# STM32.net
KiCad netlist of a schematic drawn in Altium Designer
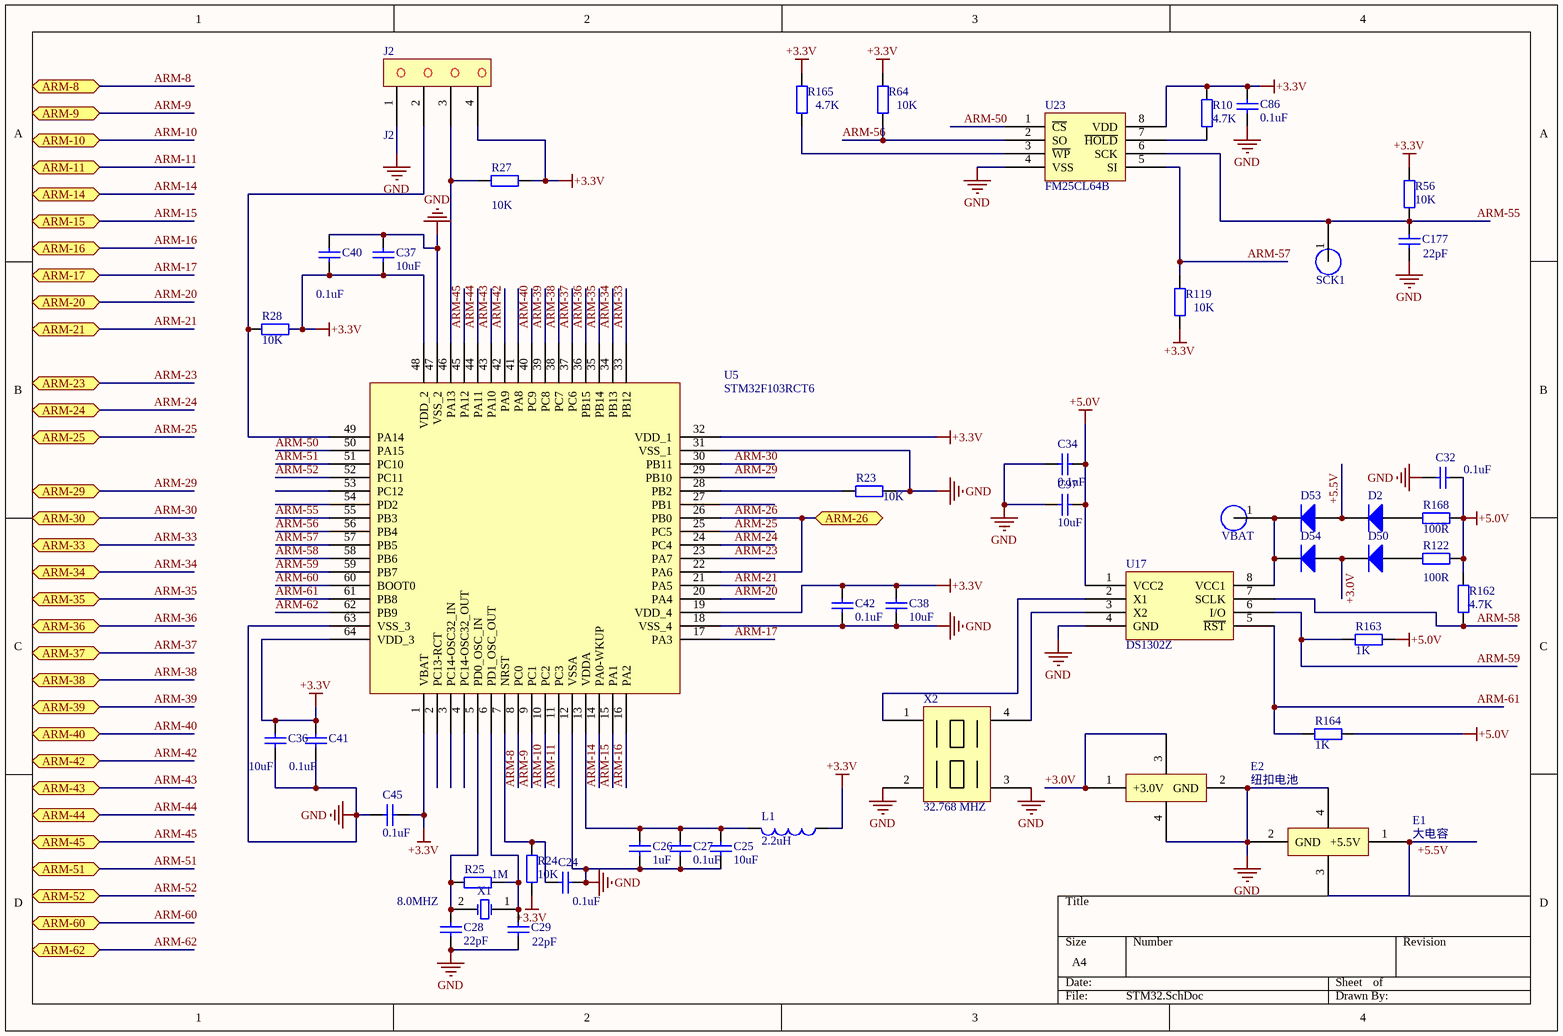
[diagram p0: STM32.SchDoc]

(export (version "E")
  (design (tool "Eeschema 10.0.6"))
  (components
    (comp (ref "C24")
      (value "0.1uF")
      (footprint "采集板3.0增加1路模拟量2:C0805")
      (description "Capacitor")
      (fields (field (name "Comment") "Cap") (field (name "PUBLISHER") "Altium Limited"))
      (libsource (lib "Miscellaneous Devices") (part "Cap"))
    )
    (comp (ref "C25")
      (value "10uF")
      (footprint "C1206")
      (description "Capacitor")
      (fields (field (name "Comment") "Cap") (field (name "PUBLISHER") "Altium Limited"))
      (libsource (lib "Miscellaneous Devices") (part "Cap"))
    )
    (comp (ref "C26")
      (value "1uF")
      (footprint "C0805")
      (description "Capacitor")
      (fields (field (name "Comment") "Cap") (field (name "PUBLISHER") "Altium Limited"))
      (libsource (lib "Miscellaneous Devices") (part "Cap"))
    )
    (comp (ref "C27")
      (value "0.1uF")
      (footprint "采集板3.0增加1路模拟量2:C0805")
      (description "Capacitor")
      (fields (field (name "Comment") "Cap") (field (name "PUBLISHER") "Altium Limited"))
      (libsource (lib "Miscellaneous Devices") (part "Cap"))
    )
    (comp (ref "C28")
      (value "22pF")
      (footprint "采集板3.0增加1路模拟量2:C0805")
      (description "Capacitor")
      (fields (field (name "Comment") "Cap") (field (name "PUBLISHER") "Altium Limited"))
      (libsource (lib "Miscellaneous Devices") (part "Cap"))
    )
    (comp (ref "C29")
      (value "22pF")
      (footprint "采集板3.0增加1路模拟量2:C0805")
      (description "Capacitor")
      (fields (field (name "Comment") "Cap") (field (name "PUBLISHER") "Altium Limited"))
      (libsource (lib "Miscellaneous Devices") (part "Cap"))
    )
    (comp (ref "C32")
      (value "0.1uF")
      (footprint "采集板3.0增加1路模拟量2:C0805")
      (description "Capacitor")
      (fields (field (name "Comment") "Cap") (field (name "PUBLISHER") "Altium Limited"))
      (libsource (lib "Miscellaneous Devices") (part "Cap"))
    )
    (comp (ref "C34")
      (value "0.1uF")
      (footprint "采集板3.0增加1路模拟量2:C0805")
      (description "Capacitor")
      (fields (field (name "Comment") "Cap") (field (name "PUBLISHER") "Altium Limited"))
      (libsource (lib "Miscellaneous Devices") (part "Cap"))
    )
    (comp (ref "C36")
      (value "10uF")
      (footprint "C1206")
      (description "Capacitor")
      (fields (field (name "Comment") "Cap") (field (name "PUBLISHER") "Altium Limited"))
      (libsource (lib "Miscellaneous Devices") (part "Cap"))
    )
    (comp (ref "C37")
      (value "10uF")
      (footprint "C1206")
      (description "Capacitor")
      (fields (field (name "Comment") "Cap") (field (name "PUBLISHER") "Altium Limited"))
      (libsource (lib "Miscellaneous Devices") (part "Cap"))
    )
    (comp (ref "C38")
      (value "10uF")
      (footprint "C1206")
      (description "Capacitor")
      (fields (field (name "Comment") "Cap") (field (name "PUBLISHER") "Altium Limited"))
      (libsource (lib "Miscellaneous Devices") (part "Cap"))
    )
    (comp (ref "C40")
      (value "0.1uF")
      (footprint "采集板3.0增加1路模拟量2:C0805")
      (description "Capacitor")
      (fields (field (name "Comment") "Cap") (field (name "PUBLISHER") "Altium Limited"))
      (libsource (lib "Miscellaneous Devices") (part "Cap"))
    )
    (comp (ref "C41")
      (value "0.1uF")
      (footprint "采集板3.0增加1路模拟量2:C0805")
      (description "Capacitor")
      (fields (field (name "Comment") "Cap") (field (name "PUBLISHER") "Altium Limited"))
      (libsource (lib "Miscellaneous Devices") (part "Cap"))
    )
    (comp (ref "C42")
      (value "0.1uF")
      (footprint "采集板3.0增加1路模拟量2:C0805")
      (description "Capacitor")
      (fields (field (name "Comment") "Cap") (field (name "PUBLISHER") "Altium Limited"))
      (libsource (lib "Miscellaneous Devices") (part "Cap"))
    )
    (comp (ref "C45")
      (value "0.1uF")
      (footprint "采集板3.0增加1路模拟量2:C0805")
      (description "Capacitor")
      (fields (field (name "Comment") "Cap") (field (name "PUBLISHER") "Altium Limited"))
      (libsource (lib "Miscellaneous Devices") (part "Cap"))
    )
    (comp (ref "C86")
      (value "0.1uF")
      (footprint "C86单独封装")
      (description "Capacitor")
      (fields (field (name "Comment") "Cap") (field (name "PUBLISHER") "Altium Limited"))
      (libsource (lib "Miscellaneous Devices") (part "Cap"))
    )
    (comp (ref "C97")
      (value "10uF")
      (footprint "C1206")
      (description "Capacitor")
      (fields (field (name "Comment") "Cap") (field (name "PUBLISHER") "Altium Limited"))
      (libsource (lib "Miscellaneous Devices") (part "Cap"))
    )
    (comp (ref "C177")
      (value "22pF")
      (footprint "采集板3.0增加1路模拟量2:C0805")
      (description "Capacitor")
      (fields (field (name "Comment") "Cap") (field (name "PUBLISHER") "Altium Limited"))
      (libsource (lib "Miscellaneous Devices") (part "Cap"))
    )
    (comp (ref "D2")
      (value "Diode 1N4001")
      (footprint "SOD123")
      (description "1 Amp General Purpose Rectifier")
      (fields (field (name "PUBLISHER") "Altium Limited"))
      (libsource (lib "Miscellaneous Devices") (part "Diode 1N4001"))
    )
    (comp (ref "D50")
      (value "Diode 1N4001")
      (footprint "SOD123")
      (description "1 Amp General Purpose Rectifier")
      (fields (field (name "PUBLISHER") "Altium Limited"))
      (libsource (lib "Miscellaneous Devices") (part "Diode 1N4001"))
    )
    (comp (ref "D53")
      (value "Diode 1N4001")
      (footprint "SOD123")
      (description "1 Amp General Purpose Rectifier")
      (fields (field (name "PUBLISHER") "Altium Limited"))
      (libsource (lib "Miscellaneous Devices") (part "Diode 1N4001"))
    )
    (comp (ref "D54")
      (value "Diode 1N4001")
      (footprint "SOD123")
      (description "1 Amp General Purpose Rectifier")
      (fields (field (name "PUBLISHER") "Altium Limited"))
      (libsource (lib "Miscellaneous Devices") (part "Diode 1N4001"))
    )
    (comp (ref "E1") (value "大电容") (footprint "法拉电容电池") (libsource (lib "大电容") (part "Component_1")))
    (comp (ref "E2") (value "纽扣电池") (footprint "法拉电容电池") (libsource (lib "纽扣电池") (part "Component_1")))
    (comp (ref "J2") (value "J2") (footprint "J2DIP") (libsource (lib "J2") (part "Component_1")))
    (comp (ref "L1")
      (value "2.2uH")
      (footprint "采集板3.0增加1路模拟量2:R0805")
      (description "Inductor")
      (fields (field (name "PUBLISHER") "Altium Limited"))
      (libsource (lib "Miscellaneous Devices") (part "Inductor"))
    )
    (comp (ref "R10")
      (value "4.7K")
      (footprint "采集板3.0增加1路模拟量2:R0805")
      (description "Resistor")
      (fields (field (name "Comment") "Res2") (field (name "PUBLISHER") "Altium Limited"))
      (libsource (lib "") (part "Res2_3"))
    )
    (comp (ref "R23")
      (value "10K")
      (footprint "采集板3.0增加1路模拟量2:R0805")
      (description "Resistor")
      (fields (field (name "Comment") "Res2") (field (name "PUBLISHER") "Altium Limited"))
      (libsource (lib "Miscellaneous Devices") (part "Res2"))
    )
    (comp (ref "R24")
      (value "10K")
      (footprint "采集板3.0增加1路模拟量2:R0805")
      (description "Resistor")
      (fields (field (name "Comment") "Res2") (field (name "PUBLISHER") "Altium Limited"))
      (libsource (lib "") (part "Res2_1"))
    )
    (comp (ref "R25")
      (value "1M")
      (footprint "采集板3.0增加1路模拟量2:R0805")
      (description "Resistor")
      (fields (field (name "Comment") "Res2") (field (name "PUBLISHER") "Altium Limited"))
      (libsource (lib "") (part "Res2_2"))
    )
    (comp (ref "R27")
      (value "10K")
      (footprint "采集板3.0增加1路模拟量2:R0805")
      (description "Resistor")
      (fields (field (name "Comment") "Res2") (field (name "PUBLISHER") "Altium Limited"))
      (libsource (lib "Miscellaneous Devices") (part "Res2"))
    )
    (comp (ref "R28")
      (value "10K")
      (footprint "采集板3.0增加1路模拟量2:R0805")
      (description "Resistor")
      (fields (field (name "Comment") "Res2") (field (name "PUBLISHER") "Altium Limited"))
      (libsource (lib "Miscellaneous Devices") (part "Res2"))
    )
    (comp (ref "R56")
      (value "10K")
      (footprint "采集板3.0增加1路模拟量2:R0805")
      (description "Resistor")
      (fields (field (name "Comment") "Res2") (field (name "PUBLISHER") "Altium Limited"))
      (libsource (lib "") (part "Res2_3"))
    )
    (comp (ref "R64")
      (value "10K")
      (footprint "采集板3.0增加1路模拟量2:R0805")
      (description "Resistor")
      (fields (field (name "Comment") "Res2") (field (name "PUBLISHER") "Altium Limited"))
      (libsource (lib "") (part "Res2_1"))
    )
    (comp (ref "R119")
      (value "10K")
      (footprint "采集板3.0增加1路模拟量2:R0805")
      (description "Resistor")
      (fields (field (name "Comment") "Res2") (field (name "PUBLISHER") "Altium Limited"))
      (libsource (lib "") (part "Res2_1"))
    )
    (comp (ref "R122")
      (value "100R")
      (footprint "R1206")
      (description "Resistor")
      (fields (field (name "Comment") "Res2") (field (name "PUBLISHER") "Altium Limited"))
      (libsource (lib "Miscellaneous Devices") (part "Res2"))
    )
    (comp (ref "R162")
      (value "4.7K")
      (footprint "采集板3.0增加1路模拟量2:R0805")
      (description "Resistor")
      (fields (field (name "Comment") "Res2") (field (name "PUBLISHER") "Altium Limited"))
      (libsource (lib "") (part "Res2_3"))
    )
    (comp (ref "R163")
      (value "1K")
      (footprint "采集板3.0增加1路模拟量2:R0805")
      (description "Resistor")
      (fields (field (name "Comment") "Res2") (field (name "PUBLISHER") "Altium Limited"))
      (libsource (lib "") (part "Res2_2"))
    )
    (comp (ref "R164")
      (value "1K")
      (footprint "采集板3.0增加1路模拟量2:R0805")
      (description "Resistor")
      (fields (field (name "Comment") "Res2") (field (name "PUBLISHER") "Altium Limited"))
      (libsource (lib "Miscellaneous Devices") (part "Res2"))
    )
    (comp (ref "R165")
      (value "4.7K")
      (footprint "采集板3.0增加1路模拟量2:R0805")
      (description "Resistor")
      (fields (field (name "Comment") "Res2") (field (name "PUBLISHER") "Altium Limited"))
      (libsource (lib "") (part "Res2_1"))
    )
    (comp (ref "R168")
      (value "100R")
      (footprint "R1206")
      (description "Resistor")
      (fields (field (name "Comment") "Res2") (field (name "PUBLISHER") "Altium Limited"))
      (libsource (lib "") (part "Res2_2"))
    )
    (comp (ref "SCK1") (value "PIN") (footprint "圆形焊盘") (libsource (lib "圆孔") (part "Component_1")))
    (comp (ref "U5")
      (value "STM32F103RCT6")
      (footprint "LQFP64")
      (libsource (lib "STM32F103RCT6") (part "Component_1"))
    )
    (comp (ref "U17") (value "DS1302Z") (footprint "SOP-8") (libsource (lib "DS1302Z") (part "Component_1")))
    (comp (ref "U23")
      (value "FM25CL64B")
      (footprint "SOIC-8")
      (libsource (lib "FM25CL64B") (part "Component_1"))
    )
    (comp (ref "VBAT") (value "PIN") (footprint "圆形焊盘") (libsource (lib "") (part "Component_1_1")))
    (comp (ref "X1")
      (value "8.0MHZ")
      (footprint "5032-2P")
      (description "Crystal Oscillator")
      (fields (field (name "Comment") "XTAL") (field (name "PUBLISHER") "Altium Limited"))
      (libsource (lib "Miscellaneous Devices") (part "XTAL"))
    )
    (comp (ref "X2")
      (value "32.768 MHZ")
      (footprint "黑色3*8-4")
      (libsource (lib "4PINXT") (part "Component_1"))
    )
  )
  (nets
    (net (code "1") (name "+3.3V") (class "Default")
      (node (ref "C36") (pin "2") (pinfunction "2_2") (pintype "passive"))
      (node (ref "C37") (pin "2") (pinfunction "2_2") (pintype "passive"))
      (node (ref "C38") (pin "2") (pinfunction "2_2") (pintype "passive"))
      (node (ref "C40") (pin "1") (pinfunction "1_1") (pintype "passive"))
      (node (ref "C41") (pin "1") (pinfunction "1_1") (pintype "passive"))
      (node (ref "C42") (pin "2") (pinfunction "2_2") (pintype "passive"))
      (node (ref "C45") (pin "1") (pinfunction "1_1") (pintype "passive"))
      (node (ref "C86") (pin "2") (pinfunction "2_2") (pintype "passive"))
      (node (ref "J2") (pin "4") (pinfunction "4_4") (pintype "passive"))
      (node (ref "L1") (pin "1") (pinfunction "1_1") (pintype "passive"))
      (node (ref "R10") (pin "1") (pinfunction "1_1") (pintype "passive"))
      (node (ref "R119") (pin "1") (pinfunction "1_1") (pintype "passive"))
      (node (ref "R165") (pin "2") (pinfunction "2_2") (pintype "passive"))
      (node (ref "R24") (pin "1") (pinfunction "1_1") (pintype "passive"))
      (node (ref "R27") (pin "2") (pinfunction "2_2") (pintype "passive"))
      (node (ref "R28") (pin "2") (pinfunction "2_2") (pintype "passive"))
      (node (ref "R56") (pin "1") (pinfunction "1_1") (pintype "passive"))
      (node (ref "R64") (pin "2") (pinfunction "2_2") (pintype "passive"))
      (node (ref "U23") (pin "8") (pinfunction "VDD_8") (pintype "passive"))
      (node (ref "U5") (pin "1") (pinfunction "VBAT_1") (pintype "passive"))
      (node (ref "U5") (pin "19") (pinfunction "VDD_4_19") (pintype "passive"))
      (node (ref "U5") (pin "32") (pinfunction "VDD_1_32") (pintype "passive"))
      (node (ref "U5") (pin "48") (pinfunction "VDD_2_48") (pintype "passive"))
      (node (ref "U5") (pin "64") (pinfunction "VDD_3_64") (pintype "passive"))
    )
    (net (code "2") (name "+5.0V") (class "Default")
      (node (ref "C32") (pin "2") (pinfunction "2_2") (pintype "passive"))
      (node (ref "C34") (pin "1") (pinfunction "1_1") (pintype "passive"))
      (node (ref "C97") (pin "1") (pinfunction "1_1") (pintype "passive"))
      (node (ref "R122") (pin "2") (pinfunction "2_2") (pintype "passive"))
      (node (ref "R162") (pin "1") (pinfunction "1_1") (pintype "passive"))
      (node (ref "R163") (pin "1") (pinfunction "1_1") (pintype "passive"))
      (node (ref "R164") (pin "2") (pinfunction "2_2") (pintype "passive"))
      (node (ref "R168") (pin "1") (pinfunction "1_1") (pintype "passive"))
      (node (ref "U17") (pin "1") (pinfunction "VCC2_1") (pintype "passive"))
    )
    (net (code "3") (name "/+3.0V") (class "Default")
      (node (ref "D50") (pin "2") (pinfunction "K_2") (pintype "passive"))
      (node (ref "D54") (pin "1") (pinfunction "A_1") (pintype "passive"))
      (node (ref "E2") (pin "1") (pinfunction "+3.0V_1") (pintype "passive"))
      (node (ref "E2") (pin "3") (pinfunction "3_3") (pintype "passive"))
    )
    (net (code "4") (name "/+5.5V") (class "Default")
      (node (ref "D2") (pin "2") (pinfunction "K_2") (pintype "passive"))
      (node (ref "D53") (pin "1") (pinfunction "A_1") (pintype "passive"))
      (node (ref "E1") (pin "1") (pinfunction "+5.5V_1") (pintype "passive"))
      (node (ref "E1") (pin "3") (pinfunction "3_3") (pintype "passive"))
    )
    (net (code "5") (name "/ARM-8") (class "Default")
      (node (ref "U5") (pin "8") (pinfunction "PC0_8") (pintype "passive"))
    )
    (net (code "6") (name "/ARM-9") (class "Default")
      (node (ref "U5") (pin "9") (pinfunction "PC1_9") (pintype "passive"))
    )
    (net (code "7") (name "/ARM-10") (class "Default")
      (node (ref "U5") (pin "10") (pinfunction "PC2_10") (pintype "passive"))
    )
    (net (code "8") (name "/ARM-11") (class "Default")
      (node (ref "U5") (pin "11") (pinfunction "PC3_11") (pintype "passive"))
    )
    (net (code "9") (name "/ARM-14") (class "Default")
      (node (ref "U5") (pin "14") (pinfunction "PA0-WKUP_14") (pintype "passive"))
    )
    (net (code "10") (name "/ARM-15") (class "Default")
      (node (ref "U5") (pin "15") (pinfunction "PA1_15") (pintype "passive"))
    )
    (net (code "11") (name "/ARM-16") (class "Default")
      (node (ref "U5") (pin "16") (pinfunction "PA2_16") (pintype "passive"))
    )
    (net (code "12") (name "/ARM-17") (class "Default")
      (node (ref "U5") (pin "17") (pinfunction "PA3_17") (pintype "passive"))
    )
    (net (code "13") (name "/ARM-20") (class "Default")
      (node (ref "U5") (pin "20") (pinfunction "PA4_20") (pintype "passive"))
    )
    (net (code "14") (name "/ARM-21") (class "Default")
      (node (ref "U5") (pin "21") (pinfunction "PA5_21") (pintype "passive"))
    )
    (net (code "15") (name "/ARM-23") (class "Default")
      (node (ref "U5") (pin "23") (pinfunction "PA7_23") (pintype "passive"))
    )
    (net (code "16") (name "/ARM-24") (class "Default")
      (node (ref "U5") (pin "24") (pinfunction "PC4_24") (pintype "passive"))
    )
    (net (code "17") (name "/ARM-25") (class "Default")
      (node (ref "U5") (pin "25") (pinfunction "PC5_25") (pintype "passive"))
    )
    (net (code "18") (name "/ARM-26") (class "Default")
      (node (ref "U5") (pin "22") (pinfunction "PA6_22") (pintype "passive"))
      (node (ref "U5") (pin "26") (pinfunction "PB0_26") (pintype "passive"))
    )
    (net (code "19") (name "/ARM-29") (class "Default")
      (node (ref "U5") (pin "29") (pinfunction "PB10_29") (pintype "passive"))
    )
    (net (code "20") (name "/ARM-30") (class "Default")
      (node (ref "U5") (pin "30") (pinfunction "PB11_30") (pintype "passive"))
    )
    (net (code "21") (name "/ARM-33") (class "Default")
      (node (ref "U5") (pin "33") (pinfunction "PB12_33") (pintype "passive"))
    )
    (net (code "22") (name "/ARM-34") (class "Default")
      (node (ref "U5") (pin "34") (pinfunction "PB13_34") (pintype "passive"))
    )
    (net (code "23") (name "/ARM-35") (class "Default")
      (node (ref "U5") (pin "35") (pinfunction "PB14_35") (pintype "passive"))
    )
    (net (code "24") (name "/ARM-36") (class "Default")
      (node (ref "U5") (pin "36") (pinfunction "PB15_36") (pintype "passive"))
    )
    (net (code "25") (name "/ARM-37") (class "Default")
      (node (ref "U5") (pin "37") (pinfunction "PC6_37") (pintype "passive"))
    )
    (net (code "26") (name "/ARM-38") (class "Default")
      (node (ref "U5") (pin "38") (pinfunction "PC7_38") (pintype "passive"))
    )
    (net (code "27") (name "/ARM-39") (class "Default")
      (node (ref "U5") (pin "39") (pinfunction "PC8_39") (pintype "passive"))
    )
    (net (code "28") (name "/ARM-40") (class "Default")
      (node (ref "U5") (pin "40") (pinfunction "PC9_40") (pintype "passive"))
    )
    (net (code "29") (name "/ARM-42") (class "Default")
      (node (ref "U5") (pin "42") (pinfunction "PA9_42") (pintype "passive"))
    )
    (net (code "30") (name "/ARM-43") (class "Default")
      (node (ref "U5") (pin "43") (pinfunction "PA10_43") (pintype "passive"))
    )
    (net (code "31") (name "/ARM-44") (class "Default")
      (node (ref "U5") (pin "44") (pinfunction "PA11_44") (pintype "passive"))
    )
    (net (code "32") (name "/ARM-45") (class "Default")
      (node (ref "U5") (pin "45") (pinfunction "PA12_45") (pintype "passive"))
    )
    (net (code "33") (name "/ARM-50") (class "Default")
      (node (ref "U23") (pin "1") (pinfunction "~{CS}_1") (pintype "passive"))
      (node (ref "U5") (pin "50") (pinfunction "PA15_50") (pintype "passive"))
    )
    (net (code "34") (name "/ARM-51") (class "Default")
      (node (ref "U5") (pin "51") (pinfunction "PC10_51") (pintype "passive"))
    )
    (net (code "35") (name "/ARM-52") (class "Default")
      (node (ref "U5") (pin "52") (pinfunction "PC11_52") (pintype "passive"))
    )
    (net (code "36") (name "/ARM-55") (class "Default")
      (node (ref "C177") (pin "1") (pinfunction "1_1") (pintype "passive"))
      (node (ref "R56") (pin "2") (pinfunction "2_2") (pintype "passive"))
      (node (ref "SCK1") (pin "1") (pinfunction "1_1") (pintype "passive"))
      (node (ref "U23") (pin "6") (pinfunction "SCK_6") (pintype "passive"))
      (node (ref "U5") (pin "55") (pinfunction "PB3_55") (pintype "passive"))
    )
    (net (code "37") (name "/ARM-56") (class "Default")
      (node (ref "R64") (pin "1") (pinfunction "1_1") (pintype "passive"))
      (node (ref "U23") (pin "2") (pinfunction "SO_2") (pintype "passive"))
      (node (ref "U5") (pin "56") (pinfunction "PB4_56") (pintype "passive"))
    )
    (net (code "38") (name "/ARM-57") (class "Default")
      (node (ref "R119") (pin "2") (pinfunction "2_2") (pintype "passive"))
      (node (ref "U23") (pin "5") (pinfunction "SI_5") (pintype "passive"))
      (node (ref "U5") (pin "57") (pinfunction "PB5_57") (pintype "passive"))
    )
    (net (code "39") (name "/ARM-58") (class "Default")
      (node (ref "R162") (pin "2") (pinfunction "2_2") (pintype "passive"))
      (node (ref "U17") (pin "7") (pinfunction "SCLK_7") (pintype "passive"))
      (node (ref "U5") (pin "58") (pinfunction "PB6_58") (pintype "passive"))
    )
    (net (code "40") (name "/ARM-59") (class "Default")
      (node (ref "R163") (pin "2") (pinfunction "2_2") (pintype "passive"))
      (node (ref "U17") (pin "6") (pinfunction "I/O_6") (pintype "passive"))
      (node (ref "U5") (pin "59") (pinfunction "PB7_59") (pintype "passive"))
    )
    (net (code "41") (name "/ARM-60") (class "Default")
      (node (ref "U5") (pin "60") (pinfunction "BOOT0_60") (pintype "passive"))
    )
    (net (code "42") (name "/ARM-61") (class "Default")
      (node (ref "R164") (pin "1") (pinfunction "1_1") (pintype "passive"))
      (node (ref "U17") (pin "5") (pinfunction "~{RST}_5") (pintype "passive"))
      (node (ref "U5") (pin "61") (pinfunction "PB8_61") (pintype "passive"))
    )
    (net (code "43") (name "/ARM-62") (class "Default")
      (node (ref "U5") (pin "62") (pinfunction "PB9_62") (pintype "passive"))
    )
    (net (code "44") (name "GND") (class "Default")
      (node (ref "C177") (pin "2") (pinfunction "2_2") (pintype "passive"))
      (node (ref "C24") (pin "1") (pinfunction "1_1") (pintype "passive"))
      (node (ref "C25") (pin "1") (pinfunction "1_1") (pintype "passive"))
      (node (ref "C26") (pin "1") (pinfunction "1_1") (pintype "passive"))
      (node (ref "C27") (pin "1") (pinfunction "1_1") (pintype "passive"))
      (node (ref "C28") (pin "2") (pinfunction "2_2") (pintype "passive"))
      (node (ref "C29") (pin "1") (pinfunction "1_1") (pintype "passive"))
      (node (ref "C32") (pin "1") (pinfunction "1_1") (pintype "passive"))
      (node (ref "C34") (pin "2") (pinfunction "2_2") (pintype "passive"))
      (node (ref "C36") (pin "1") (pinfunction "1_1") (pintype "passive"))
      (node (ref "C37") (pin "1") (pinfunction "1_1") (pintype "passive"))
      (node (ref "C38") (pin "1") (pinfunction "1_1") (pintype "passive"))
      (node (ref "C40") (pin "2") (pinfunction "2_2") (pintype "passive"))
      (node (ref "C41") (pin "2") (pinfunction "2_2") (pintype "passive"))
      (node (ref "C42") (pin "1") (pinfunction "1_1") (pintype "passive"))
      (node (ref "C45") (pin "2") (pinfunction "2_2") (pintype "passive"))
      (node (ref "C86") (pin "1") (pinfunction "1_1") (pintype "passive"))
      (node (ref "C97") (pin "2") (pinfunction "2_2") (pintype "passive"))
      (node (ref "E1") (pin "2") (pinfunction "GND_2") (pintype "passive"))
      (node (ref "E1") (pin "4") (pinfunction "4_4") (pintype "passive"))
      (node (ref "E2") (pin "2") (pinfunction "GND_2") (pintype "passive"))
      (node (ref "E2") (pin "4") (pinfunction "4_4") (pintype "passive"))
      (node (ref "J2") (pin "1") (pinfunction "1_1") (pintype "passive"))
      (node (ref "R23") (pin "2") (pinfunction "2_2") (pintype "passive"))
      (node (ref "U17") (pin "4") (pinfunction "GND_4") (pintype "passive"))
      (node (ref "U23") (pin "4") (pinfunction "VSS_4") (pintype "passive"))
      (node (ref "U5") (pin "12") (pinfunction "VSSA_12") (pintype "passive"))
      (node (ref "U5") (pin "18") (pinfunction "VSS_4_18") (pintype "passive"))
      (node (ref "U5") (pin "31") (pinfunction "VSS_1_31") (pintype "passive"))
      (node (ref "U5") (pin "47") (pinfunction "VSS_2_47") (pintype "passive"))
      (node (ref "U5") (pin "63") (pinfunction "VSS_3_63") (pintype "passive"))
      (node (ref "X2") (pin "2") (pinfunction "2_2") (pintype "passive"))
      (node (ref "X2") (pin "3") (pinfunction "3_3") (pintype "passive"))
    )
    (net (code "45") (name "Net-(D2-A)") (class "Default")
      (node (ref "D2") (pin "1") (pinfunction "A_1") (pintype "passive"))
      (node (ref "R168") (pin "2") (pinfunction "2_2") (pintype "passive"))
    )
    (net (code "46") (name "Net-(D50-A)") (class "Default")
      (node (ref "D50") (pin "1") (pinfunction "A_1") (pintype "passive"))
      (node (ref "R122") (pin "1") (pinfunction "1_1") (pintype "passive"))
    )
    (net (code "47") (name "Net-(D53-K)") (class "Default")
      (node (ref "D53") (pin "2") (pinfunction "K_2") (pintype "passive"))
      (node (ref "D54") (pin "2") (pinfunction "K_2") (pintype "passive"))
      (node (ref "U17") (pin "8") (pinfunction "VCC1_8") (pintype "passive"))
      (node (ref "VBAT") (pin "1") (pinfunction "1_1") (pintype "passive"))
    )
    (net (code "48") (name "Net-(U5-NRST)") (class "Default")
      (node (ref "C24") (pin "2") (pinfunction "2_2") (pintype "passive"))
      (node (ref "R24") (pin "2") (pinfunction "2_2") (pintype "passive"))
      (node (ref "U5") (pin "7") (pinfunction "NRST_7") (pintype "passive"))
    )
    (net (code "49") (name "Net-(U5-PA13)") (class "Default")
      (node (ref "J2") (pin "3") (pinfunction "3_3") (pintype "passive"))
      (node (ref "R27") (pin "1") (pinfunction "1_1") (pintype "passive"))
      (node (ref "U5") (pin "46") (pinfunction "PA13_46") (pintype "passive"))
    )
    (net (code "50") (name "Net-(U5-PA14)") (class "Default")
      (node (ref "J2") (pin "2") (pinfunction "2_2") (pintype "passive"))
      (node (ref "R28") (pin "1") (pinfunction "1_1") (pintype "passive"))
      (node (ref "U5") (pin "49") (pinfunction "PA14_49") (pintype "passive"))
    )
    (net (code "51") (name "Net-(U5-PB2)") (class "Default")
      (node (ref "R23") (pin "1") (pinfunction "1_1") (pintype "passive"))
      (node (ref "U5") (pin "28") (pinfunction "PB2_28") (pintype "passive"))
    )
    (net (code "52") (name "Net-(U5-PD0_OSC_IN)") (class "Default")
      (node (ref "C28") (pin "1") (pinfunction "1_1") (pintype "passive"))
      (node (ref "R25") (pin "2") (pinfunction "2_2") (pintype "passive"))
      (node (ref "U5") (pin "5") (pinfunction "PD0_OSC_IN_5") (pintype "passive"))
      (node (ref "X1") (pin "2") (pinfunction "OSC2_2") (pintype "passive"))
    )
    (net (code "53") (name "Net-(U5-PD1_OSC_OUT)") (class "Default")
      (node (ref "C29") (pin "2") (pinfunction "2_2") (pintype "passive"))
      (node (ref "R25") (pin "1") (pinfunction "1_1") (pintype "passive"))
      (node (ref "U5") (pin "6") (pinfunction "PD1_OSC_OUT_6") (pintype "passive"))
      (node (ref "X1") (pin "1") (pinfunction "OSC1_1") (pintype "passive"))
    )
    (net (code "54") (name "Net-(U5-VDDA)") (class "Default")
      (node (ref "C25") (pin "2") (pinfunction "2_2") (pintype "passive"))
      (node (ref "C26") (pin "2") (pinfunction "2_2") (pintype "passive"))
      (node (ref "C27") (pin "2") (pinfunction "2_2") (pintype "passive"))
      (node (ref "L1") (pin "2") (pinfunction "2_2") (pintype "passive"))
      (node (ref "U5") (pin "13") (pinfunction "VDDA_13") (pintype "passive"))
    )
    (net (code "55") (name "Net-(U17-X1)") (class "Default")
      (node (ref "U17") (pin "2") (pinfunction "X1_2") (pintype "passive"))
      (node (ref "X2") (pin "1") (pinfunction "1_1") (pintype "passive"))
    )
    (net (code "56") (name "Net-(U17-X2)") (class "Default")
      (node (ref "U17") (pin "3") (pinfunction "X2_3") (pintype "passive"))
      (node (ref "X2") (pin "4") (pinfunction "4_4") (pintype "passive"))
    )
    (net (code "57") (name "Net-(U23-~{HOLD})") (class "Default")
      (node (ref "R10") (pin "2") (pinfunction "2_2") (pintype "passive"))
      (node (ref "U23") (pin "7") (pinfunction "~{HOLD}_7") (pintype "passive"))
    )
    (net (code "58") (name "Net-(U23-~{WP})") (class "Default")
      (node (ref "R165") (pin "1") (pinfunction "1_1") (pintype "passive"))
      (node (ref "U23") (pin "3") (pinfunction "~{WP}_3") (pintype "passive"))
    )
    (net (code "59") (name "unconnected-(U5-PA8-Pad41)") (class "Default")
      (node (ref "U5") (pin "41") (pinfunction "PA8_41") (pintype "passive"))
    )
    (net (code "60") (name "unconnected-(U5-PB1-Pad27)") (class "Default")
      (node (ref "U5") (pin "27") (pinfunction "PB1_27") (pintype "passive"))
    )
    (net (code "61") (name "unconnected-(U5-PC12-Pad53)") (class "Default")
      (node (ref "U5") (pin "53") (pinfunction "PC12_53") (pintype "passive"))
    )
    (net (code "62") (name "unconnected-(U5-PC13-RCT-Pad2)") (class "Default")
      (node (ref "U5") (pin "2") (pinfunction "PC13-RCT_2") (pintype "passive"))
    )
    (net (code "63") (name "unconnected-(U5-PC14-OSC32_IN-Pad3)") (class "Default")
      (node (ref "U5") (pin "3") (pinfunction "PC14-OSC32_IN_3") (pintype "passive"))
    )
    (net (code "64") (name "unconnected-(U5-PC14-OSC32_OUT-Pad4)") (class "Default")
      (node (ref "U5") (pin "4") (pinfunction "PC14-OSC32_OUT_4") (pintype "passive"))
    )
    (net (code "65") (name "unconnected-(U5-PD2-Pad54)") (class "Default")
      (node (ref "U5") (pin "54") (pinfunction "PD2_54") (pintype "passive"))
    )
  )
)
